# MAIN.net
KiCad netlist of a schematic drawn in Altium Designer
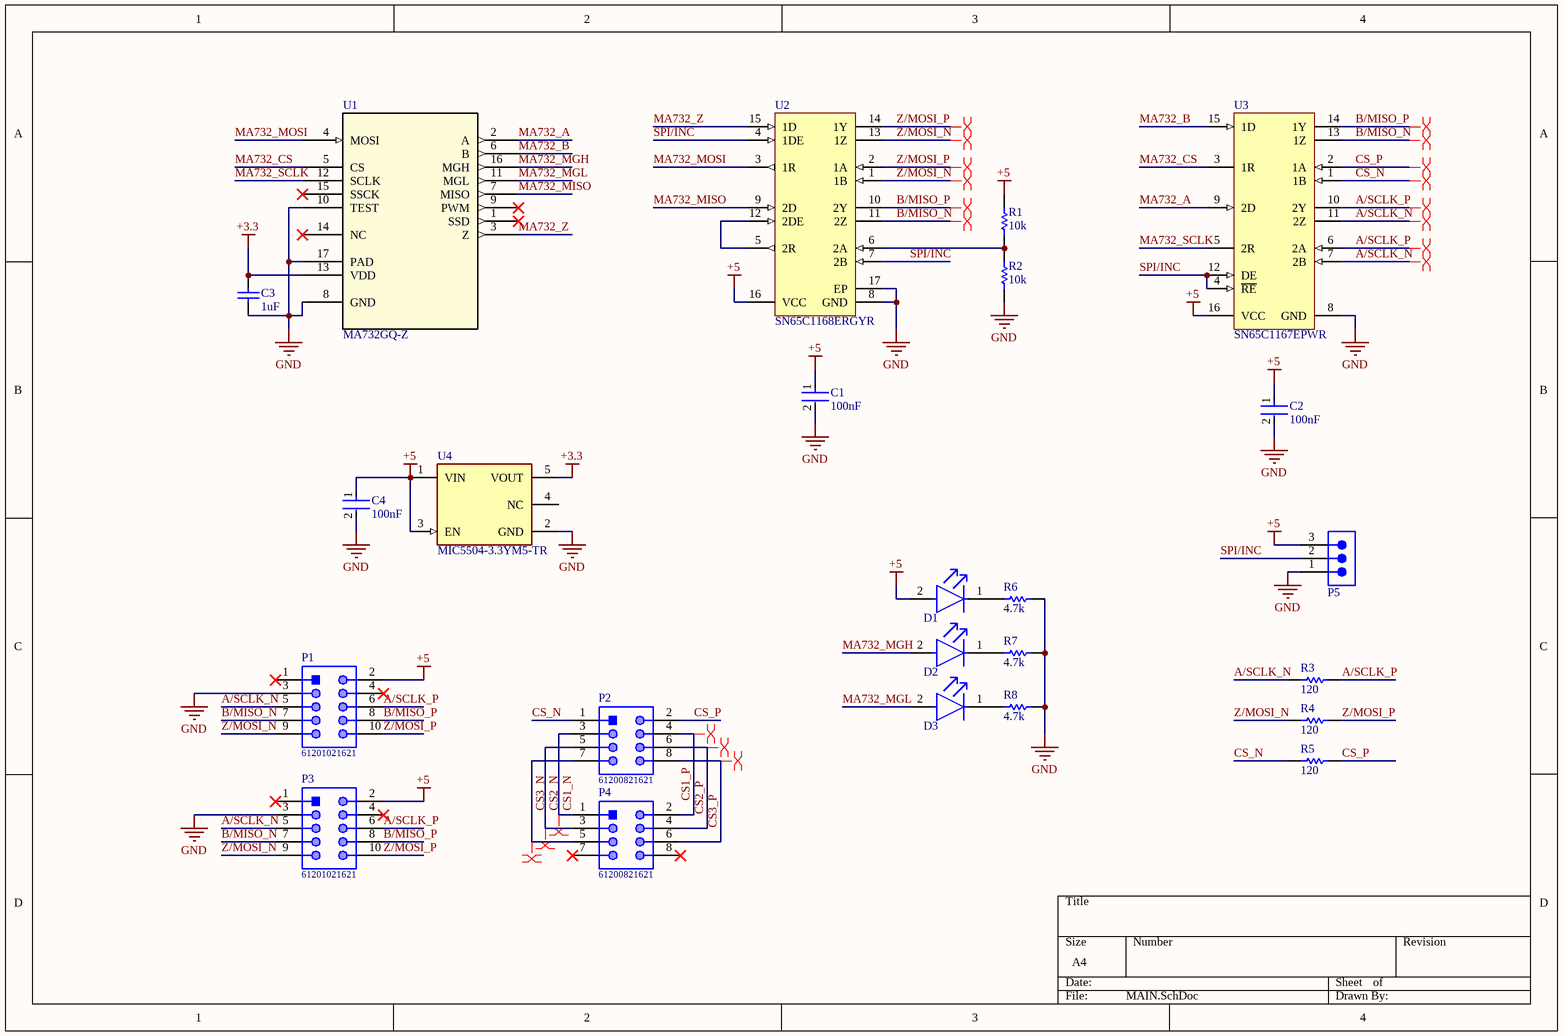
[diagram p0: MAIN.SchDoc]

(export (version "E")
  (design (tool "Eeschema 10.0.6"))
  (components
    (comp (ref "C1")
      (value "100nF")
      (footprint "FP-C0805C-DN-MFG")
      (description "CAP CER 0.1UF 50V X7R 0805")
      (fields
        (field (name "MANUFACTURER PART NUMBER") "C0805C104K5RACTU")
        (field (name "MANUFACTURER") "KEMET")
      )
      (libsource (lib "Altium Content Vault") (part "b4654b650e69147ec39a6b967a45e02"))
    )
    (comp (ref "C2")
      (value "100nF")
      (footprint "FP-C0805C-DN-MFG")
      (description "CAP CER 0.1UF 50V X7R 0805")
      (fields
        (field (name "MANUFACTURER PART NUMBER") "C0805C104K5RACTU")
        (field (name "MANUFACTURER") "KEMET")
      )
      (libsource (lib "Altium Content Vault") (part "b4654b650e69147ec39a6b967a45e02"))
    )
    (comp (ref "C3")
      (value "1uF")
      (footprint "CAPC2013X70X45NL10T25")
      (fields (field (name "PART NUMBER") "GRM216R61E105KA12D") (field (name "MANUFACTURER") "Murata"))
      (libsource (lib "Altium Content Vault") (part "CAP"))
    )
    (comp (ref "C4")
      (value "100nF")
      (footprint "FP-C0805C-DN-MFG")
      (description "CAP CER 0.1UF 50V X7R 0805")
      (fields
        (field (name "MANUFACTURER PART NUMBER") "C0805C104K5RACTU")
        (field (name "MANUFACTURER") "KEMET")
      )
      (libsource (lib "Altium Content Vault") (part "b4654b650e69147ec39a6b967a45e02"))
    )
    (comp (ref "D1")
      (value "150080SS75000")
      (footprint "FP-150080SS75000-MFG")
      (description "LED RED CLEAR 0805 SMD")
      (libsource (lib "Altium Content Vault") (part "8706943c75ba83719d021d2fdc84c58"))
    )
    (comp (ref "D2")
      (value "150080SS75000")
      (footprint "FP-150080SS75000-MFG")
      (description "LED RED CLEAR 0805 SMD")
      (libsource (lib "Altium Content Vault") (part "8706943c75ba83719d021d2fdc84c58"))
    )
    (comp (ref "D3")
      (value "150080SS75000")
      (footprint "FP-150080SS75000-MFG")
      (description "LED RED CLEAR 0805 SMD")
      (libsource (lib "Altium Content Vault") (part "8706943c75ba83719d021d2fdc84c58"))
    )
    (comp (ref "P1")
      (value "61201021621")
      (footprint "61201021621")
      (description "Male Box Header WR-BHD, THT, Vertical, pitch 2.54 mm, 10 pins")
      (fields (field (name "MANUFACTURER") "Wurth Elektronik") (field (name "PUBLISHER") "WurthElektronik"))
      (libsource (lib "Altium Content Vault") (part "WE-CN-2P-M-R10"))
    )
    (comp (ref "P2")
      (value "61200821621")
      (footprint "61200821621")
      (description "Male Box Header WR-BHD, THT, Vertical, pitch 2.54 mm, 8 pins")
      (fields (field (name "MANUFACTURER") "Wurth Elektronik") (field (name "PUBLISHER") "WurthElektronik"))
      (libsource (lib "Altium Content Vault") (part "WE-CN-2P-M-R8"))
    )
    (comp (ref "P3")
      (value "61201021621")
      (footprint "61201021621")
      (description "Male Box Header WR-BHD, THT, Vertical, pitch 2.54 mm, 10 pins")
      (fields (field (name "MANUFACTURER") "Wurth Elektronik") (field (name "PUBLISHER") "WurthElektronik"))
      (libsource (lib "Altium Content Vault") (part "WE-CN-2P-M-R10"))
    )
    (comp (ref "P4")
      (value "61200821621")
      (footprint "61200821621")
      (description "Male Box Header WR-BHD, THT, Vertical, pitch 2.54 mm, 8 pins")
      (fields (field (name "MANUFACTURER") "Wurth Elektronik") (field (name "PUBLISHER") "WurthElektronik"))
      (libsource (lib "Altium Content Vault") (part "WE-CN-2P-M-R8"))
    )
    (comp (ref "P5")
      (value "TSW-103-07-T-S")
      (footprint "SMTC-TSW-103-07-X-S")
      (description "0.025\" SQ Post Header, Through-hole, Vertical, -55 to 105 degC, 2.54 mm Pitch, 3-Pin, Male, RoHS")
      (fields (field (name "MANUFACTURER") "Samtec"))
      (libsource (lib "Altium Content Vault") (part "SMTC-TSW-103-X-X-S-X"))
    )
    (comp (ref "R1")
      (value "10k")
      (footprint "RESC2013X60X40LL20T25_A")
      (fields (field (name "TOLERANCE") "0.1%") (field (name "MANUFACTURER") "Panasonic"))
      (libsource (lib "Altium Content Vault") (part "RES-2"))
    )
    (comp (ref "R2")
      (value "10k")
      (footprint "RESC2013X60X40LL20T25_A")
      (fields (field (name "TOLERANCE") "0.1%") (field (name "MANUFACTURER") "Panasonic"))
      (libsource (lib "Altium Content Vault") (part "RES-2"))
    )
    (comp (ref "R3")
      (value "120")
      (footprint "RESC2013X60X40ML20T25")
      (fields (field (name "MANUFACTURER") "Panasonic") (field (name "PART NUMBER") "ERA6AEB121V"))
      (libsource (lib "Altium Content Vault") (part "RES"))
    )
    (comp (ref "R4")
      (value "120")
      (footprint "RESC2013X60X40ML20T25")
      (fields (field (name "MANUFACTURER") "Panasonic") (field (name "PART NUMBER") "ERA6AEB121V"))
      (libsource (lib "Altium Content Vault") (part "RES"))
    )
    (comp (ref "R5")
      (value "120")
      (footprint "RESC2013X60X40ML20T25")
      (fields (field (name "MANUFACTURER") "Panasonic") (field (name "PART NUMBER") "ERA6AEB121V"))
      (libsource (lib "Altium Content Vault") (part "RES"))
    )
    (comp (ref "R6")
      (value "4.7k")
      (footprint "RESC2013X70X40NL20T20")
      (description "Chip Resistor, 4.7 KOhm, +/- 1%, 0.125 W, -55 to 155 degC, 0805 (2012 Metric), RoHS, Tape and Reel")
      (fields (field (name "MANUFACTURER") "Panasonic"))
      (libsource (lib "Altium Content Vault") (part "RES-2"))
    )
    (comp (ref "R7")
      (value "4.7k")
      (footprint "RESC2013X70X40NL20T20")
      (description "Chip Resistor, 4.7 KOhm, +/- 1%, 0.125 W, -55 to 155 degC, 0805 (2012 Metric), RoHS, Tape and Reel")
      (fields (field (name "MANUFACTURER") "Panasonic"))
      (libsource (lib "Altium Content Vault") (part "RES-2"))
    )
    (comp (ref "R8")
      (value "4.7k")
      (footprint "RESC2013X70X40NL20T20")
      (description "Chip Resistor, 4.7 KOhm, +/- 1%, 0.125 W, -55 to 155 degC, 0805 (2012 Metric), RoHS, Tape and Reel")
      (fields (field (name "MANUFACTURER") "Panasonic"))
      (libsource (lib "Altium Content Vault") (part "RES-2"))
    )
    (comp (ref "U1")
      (value "MA732GQ-Z")
      (footprint "QFN-16_MA732")
      (description "No Description Available")
      (fields (field (name "COPYRIGHT") "Copyright (C) 2023 Ultra Librarian. All rights reserved."))
      (libsource (lib "MA732GQ-Z") (part "MA732GQ-Z"))
    )
    (comp (ref "U2")
      (value "SN65C1168ERGYR")
      (footprint "RGY0016A_V")
      (description "None")
      (libsource (lib "Altium Content Vault") (part "TI-SN65C1168E-VQFN_RGY-16"))
    )
    (comp (ref "U3")
      (value "SN65C1167EPWR")
      (footprint "PW0016A_M")
      (fields (field (name "MANUFACTURER") "Texas Instruments"))
      (libsource (lib "Altium Content Vault") (part "TI-SN65C1167E-TSSOP_PW-16"))
    )
    (comp (ref "U4")
      (value "MIC5504-3.3YM5-TR")
      (footprint "FP-SOT23-5LD-PL-1-MFG")
      (description "IC REG LINEAR 3.3V 300MA SOT23-5")
      (libsource (lib "Altium Content Vault") (part "96048095611b4a9579e1e315950d302"))
    )
  )
  (nets
    (net (code "1") (name "+3.3") (class "Default")
      (node (ref "C3") (pin "2") (pinfunction "2_2") (pintype "passive"))
      (node (ref "U1") (pin "13") (pinfunction "VDD_13") (pintype "power_in"))
      (node (ref "U4") (pin "5") (pinfunction "VOUT_5") (pintype "power_in"))
    )
    (net (code "2") (name "+5") (class "Default")
      (node (ref "C1") (pin "1") (pinfunction "1_1") (pintype "passive"))
      (node (ref "C2") (pin "1") (pinfunction "1_1") (pintype "passive"))
      (node (ref "C4") (pin "1") (pinfunction "1_1") (pintype "passive"))
      (node (ref "D1") (pin "2") (pinfunction "A_2") (pintype "passive"))
      (node (ref "P1") (pin "2") (pinfunction "2_2") (pintype "passive"))
      (node (ref "P3") (pin "2") (pinfunction "2_2") (pintype "passive"))
      (node (ref "P5") (pin "3") (pinfunction "3_3") (pintype "passive"))
      (node (ref "R1") (pin "2") (pinfunction "2_2") (pintype "passive"))
      (node (ref "U2") (pin "16") (pinfunction "VCC_16") (pintype "power_in"))
      (node (ref "U3") (pin "16") (pinfunction "VCC_16") (pintype "power_in"))
      (node (ref "U4") (pin "1") (pinfunction "VIN_1") (pintype "power_in"))
      (node (ref "U4") (pin "3") (pinfunction "EN_3") (pintype "input"))
    )
    (net (code "3") (name "/A{slash}SCLK_N") (class "Default")
      (node (ref "P1") (pin "5") (pinfunction "5_5") (pintype "passive"))
      (node (ref "P3") (pin "5") (pinfunction "5_5") (pintype "passive"))
      (node (ref "R3") (pin "1") (pinfunction "1_1") (pintype "passive"))
      (node (ref "U3") (pin "11") (pinfunction "2Z_11") (pintype "tri_state"))
      (node (ref "U3") (pin "7") (pinfunction "2B_7") (pintype "input"))
    )
    (net (code "4") (name "/A{slash}SCLK_P") (class "Default")
      (node (ref "P1") (pin "6") (pinfunction "6_6") (pintype "passive"))
      (node (ref "P3") (pin "6") (pinfunction "6_6") (pintype "passive"))
      (node (ref "R3") (pin "2") (pinfunction "2_2") (pintype "passive"))
      (node (ref "U3") (pin "10") (pinfunction "2Y_10") (pintype "tri_state"))
      (node (ref "U3") (pin "6") (pinfunction "2A_6") (pintype "input"))
    )
    (net (code "5") (name "/B{slash}MISO_N") (class "Default")
      (node (ref "P1") (pin "7") (pinfunction "7_7") (pintype "passive"))
      (node (ref "P3") (pin "7") (pinfunction "7_7") (pintype "passive"))
      (node (ref "U2") (pin "11") (pinfunction "2Z_11") (pintype "tri_state"))
      (node (ref "U3") (pin "13") (pinfunction "1Z_13") (pintype "tri_state"))
    )
    (net (code "6") (name "/B{slash}MISO_P") (class "Default")
      (node (ref "P1") (pin "8") (pinfunction "8_8") (pintype "passive"))
      (node (ref "P3") (pin "8") (pinfunction "8_8") (pintype "passive"))
      (node (ref "U2") (pin "10") (pinfunction "2Y_10") (pintype "tri_state"))
      (node (ref "U3") (pin "14") (pinfunction "1Y_14") (pintype "tri_state"))
    )
    (net (code "7") (name "/CS1_N") (class "Default")
      (node (ref "P2") (pin "3") (pinfunction "3_3") (pintype "passive"))
      (node (ref "P4") (pin "1") (pinfunction "1_1") (pintype "passive"))
    )
    (net (code "8") (name "/CS1_P") (class "Default")
      (node (ref "P2") (pin "4") (pinfunction "4_4") (pintype "passive"))
      (node (ref "P4") (pin "2") (pinfunction "2_2") (pintype "passive"))
    )
    (net (code "9") (name "/CS2_N") (class "Default")
      (node (ref "P2") (pin "5") (pinfunction "5_5") (pintype "passive"))
      (node (ref "P4") (pin "3") (pinfunction "3_3") (pintype "passive"))
    )
    (net (code "10") (name "/CS2_P") (class "Default")
      (node (ref "P2") (pin "6") (pinfunction "6_6") (pintype "passive"))
      (node (ref "P4") (pin "4") (pinfunction "4_4") (pintype "passive"))
    )
    (net (code "11") (name "/CS3_N") (class "Default")
      (node (ref "P2") (pin "7") (pinfunction "7_7") (pintype "passive"))
      (node (ref "P4") (pin "5") (pinfunction "5_5") (pintype "passive"))
    )
    (net (code "12") (name "/CS3_P") (class "Default")
      (node (ref "P2") (pin "8") (pinfunction "8_8") (pintype "passive"))
      (node (ref "P4") (pin "6") (pinfunction "6_6") (pintype "passive"))
    )
    (net (code "13") (name "/CS_N") (class "Default")
      (node (ref "P2") (pin "1") (pinfunction "1_1") (pintype "passive"))
      (node (ref "R5") (pin "1") (pinfunction "1_1") (pintype "passive"))
      (node (ref "U3") (pin "1") (pinfunction "1B_1") (pintype "input"))
    )
    (net (code "14") (name "/CS_P") (class "Default")
      (node (ref "P2") (pin "2") (pinfunction "2_2") (pintype "passive"))
      (node (ref "R5") (pin "2") (pinfunction "2_2") (pintype "passive"))
      (node (ref "U3") (pin "2") (pinfunction "1A_2") (pintype "input"))
    )
    (net (code "15") (name "/MA732_A") (class "Default")
      (node (ref "U1") (pin "2") (pinfunction "A_2") (pintype "output"))
      (node (ref "U3") (pin "9") (pinfunction "2D_9") (pintype "input"))
    )
    (net (code "16") (name "/MA732_B") (class "Default")
      (node (ref "U1") (pin "6") (pinfunction "B_6") (pintype "output"))
      (node (ref "U3") (pin "15") (pinfunction "1D_15") (pintype "input"))
    )
    (net (code "17") (name "/MA732_CS") (class "Default")
      (node (ref "U1") (pin "5") (pinfunction "CS_5") (pintype "passive"))
      (node (ref "U3") (pin "3") (pinfunction "1R_3") (pintype "tri_state"))
    )
    (net (code "18") (name "/MA732_MGH") (class "Default")
      (node (ref "D2") (pin "2") (pinfunction "A_2") (pintype "passive"))
      (node (ref "U1") (pin "16") (pinfunction "MGH_16") (pintype "output"))
    )
    (net (code "19") (name "/MA732_MGL") (class "Default")
      (node (ref "D3") (pin "2") (pinfunction "A_2") (pintype "passive"))
      (node (ref "U1") (pin "11") (pinfunction "MGL_11") (pintype "output"))
    )
    (net (code "20") (name "/MA732_MISO") (class "Default")
      (node (ref "U1") (pin "7") (pinfunction "MISO_7") (pintype "output"))
      (node (ref "U2") (pin "9") (pinfunction "2D_9") (pintype "input"))
    )
    (net (code "21") (name "/MA732_MOSI") (class "Default")
      (node (ref "U1") (pin "4") (pinfunction "MOSI_4") (pintype "input"))
      (node (ref "U2") (pin "3") (pinfunction "1R_3") (pintype "output"))
    )
    (net (code "22") (name "/MA732_SCLK") (class "Default")
      (node (ref "U1") (pin "12") (pinfunction "SCLK_12") (pintype "passive"))
      (node (ref "U3") (pin "5") (pinfunction "2R_5") (pintype "tri_state"))
    )
    (net (code "23") (name "/MA732_Z") (class "Default")
      (node (ref "U1") (pin "3") (pinfunction "Z_3") (pintype "output"))
      (node (ref "U2") (pin "15") (pinfunction "1D_15") (pintype "input"))
    )
    (net (code "24") (name "/SPI{slash}INC") (class "Default")
      (node (ref "P5") (pin "2") (pinfunction "2_2") (pintype "passive"))
      (node (ref "U2") (pin "4") (pinfunction "1DE_4") (pintype "input"))
      (node (ref "U2") (pin "7") (pinfunction "2B_7") (pintype "input"))
      (node (ref "U3") (pin "12") (pinfunction "DE_12") (pintype "input"))
      (node (ref "U3") (pin "4") (pinfunction "~{RE}_4") (pintype "input"))
    )
    (net (code "25") (name "/Z{slash}MOSI_N") (class "Default")
      (node (ref "P1") (pin "9") (pinfunction "9_9") (pintype "passive"))
      (node (ref "P3") (pin "9") (pinfunction "9_9") (pintype "passive"))
      (node (ref "R4") (pin "1") (pinfunction "1_1") (pintype "passive"))
      (node (ref "U2") (pin "1") (pinfunction "1B_1") (pintype "input"))
      (node (ref "U2") (pin "13") (pinfunction "1Z_13") (pintype "tri_state"))
    )
    (net (code "26") (name "/Z{slash}MOSI_P") (class "Default")
      (node (ref "P1") (pin "10") (pinfunction "10_10") (pintype "passive"))
      (node (ref "P3") (pin "10") (pinfunction "10_10") (pintype "passive"))
      (node (ref "R4") (pin "2") (pinfunction "2_2") (pintype "passive"))
      (node (ref "U2") (pin "14") (pinfunction "1Y_14") (pintype "tri_state"))
      (node (ref "U2") (pin "2") (pinfunction "1A_2") (pintype "input"))
    )
    (net (code "27") (name "GND") (class "Default")
      (node (ref "C1") (pin "2") (pinfunction "2_2") (pintype "passive"))
      (node (ref "C2") (pin "2") (pinfunction "2_2") (pintype "passive"))
      (node (ref "C3") (pin "1") (pinfunction "1_1") (pintype "passive"))
      (node (ref "C4") (pin "2") (pinfunction "2_2") (pintype "passive"))
      (node (ref "P1") (pin "3") (pinfunction "3_3") (pintype "passive"))
      (node (ref "P3") (pin "3") (pinfunction "3_3") (pintype "passive"))
      (node (ref "P5") (pin "1") (pinfunction "1_1") (pintype "passive"))
      (node (ref "R2") (pin "1") (pinfunction "1_1") (pintype "passive"))
      (node (ref "R6") (pin "2") (pinfunction "2_2") (pintype "passive"))
      (node (ref "R7") (pin "2") (pinfunction "2_2") (pintype "passive"))
      (node (ref "R8") (pin "2") (pinfunction "2_2") (pintype "passive"))
      (node (ref "U1") (pin "10") (pinfunction "TEST_10") (pintype "passive"))
      (node (ref "U1") (pin "17") (pinfunction "PAD_17") (pintype "power_in"))
      (node (ref "U1") (pin "8") (pinfunction "GND_8") (pintype "power_in"))
      (node (ref "U2") (pin "17") (pinfunction "EP_17") (pintype "passive"))
      (node (ref "U2") (pin "8") (pinfunction "GND_8") (pintype "power_in"))
      (node (ref "U3") (pin "8") (pinfunction "GND_8") (pintype "power_in"))
      (node (ref "U4") (pin "2") (pinfunction "GND_2") (pintype "power_in"))
    )
    (net (code "28") (name "Net-(D1-C)") (class "Default")
      (node (ref "D1") (pin "1") (pinfunction "C_1") (pintype "passive"))
      (node (ref "R6") (pin "1") (pinfunction "1_1") (pintype "passive"))
    )
    (net (code "29") (name "Net-(D2-C)") (class "Default")
      (node (ref "D2") (pin "1") (pinfunction "C_1") (pintype "passive"))
      (node (ref "R7") (pin "1") (pinfunction "1_1") (pintype "passive"))
    )
    (net (code "30") (name "Net-(D3-C)") (class "Default")
      (node (ref "D3") (pin "1") (pinfunction "C_1") (pintype "passive"))
      (node (ref "R8") (pin "1") (pinfunction "1_1") (pintype "passive"))
    )
    (net (code "31") (name "Net-(U2-2A)") (class "Default")
      (node (ref "R1") (pin "1") (pinfunction "1_1") (pintype "passive"))
      (node (ref "R2") (pin "2") (pinfunction "2_2") (pintype "passive"))
      (node (ref "U2") (pin "6") (pinfunction "2A_6") (pintype "input"))
    )
    (net (code "32") (name "Net-(U2-2DE)") (class "Default")
      (node (ref "U2") (pin "12") (pinfunction "2DE_12") (pintype "input"))
      (node (ref "U2") (pin "5") (pinfunction "2R_5") (pintype "output"))
    )
    (net (code "33") (name "unconnected-(P1-Pad1)") (class "Default")
      (node (ref "P1") (pin "1") (pinfunction "1_1") (pintype "passive+no_connect"))
    )
    (net (code "34") (name "unconnected-(P1-Pad4)") (class "Default")
      (node (ref "P1") (pin "4") (pinfunction "4_4") (pintype "passive+no_connect"))
    )
    (net (code "35") (name "unconnected-(P3-Pad1)") (class "Default")
      (node (ref "P3") (pin "1") (pinfunction "1_1") (pintype "passive+no_connect"))
    )
    (net (code "36") (name "unconnected-(P3-Pad4)") (class "Default")
      (node (ref "P3") (pin "4") (pinfunction "4_4") (pintype "passive+no_connect"))
    )
    (net (code "37") (name "unconnected-(P4-Pad7)") (class "Default")
      (node (ref "P4") (pin "7") (pinfunction "7_7") (pintype "passive+no_connect"))
    )
    (net (code "38") (name "unconnected-(P4-Pad8)") (class "Default")
      (node (ref "P4") (pin "8") (pinfunction "8_8") (pintype "passive+no_connect"))
    )
    (net (code "39") (name "unconnected-(U1-NC-Pad14)") (class "Default")
      (node (ref "U1") (pin "14") (pinfunction "NC_14") (pintype "passive+no_connect"))
    )
    (net (code "40") (name "unconnected-(U1-PWM-Pad9)") (class "Default")
      (node (ref "U1") (pin "9") (pinfunction "PWM_9") (pintype "output+no_connect"))
    )
    (net (code "41") (name "unconnected-(U1-SSCK-Pad15)") (class "Default")
      (node (ref "U1") (pin "15") (pinfunction "SSCK_15") (pintype "passive+no_connect"))
    )
    (net (code "42") (name "unconnected-(U1-SSD-Pad1)") (class "Default")
      (node (ref "U1") (pin "1") (pinfunction "SSD_1") (pintype "output+no_connect"))
    )
    (net (code "43") (name "unconnected-(U4-NC-Pad4)") (class "Default")
      (node (ref "U4") (pin "4") (pinfunction "NC_4") (pintype "passive"))
    )
  )
)
